# EPS_Local-Supply.net
KiCad netlist of a schematic drawn in Altium Designer
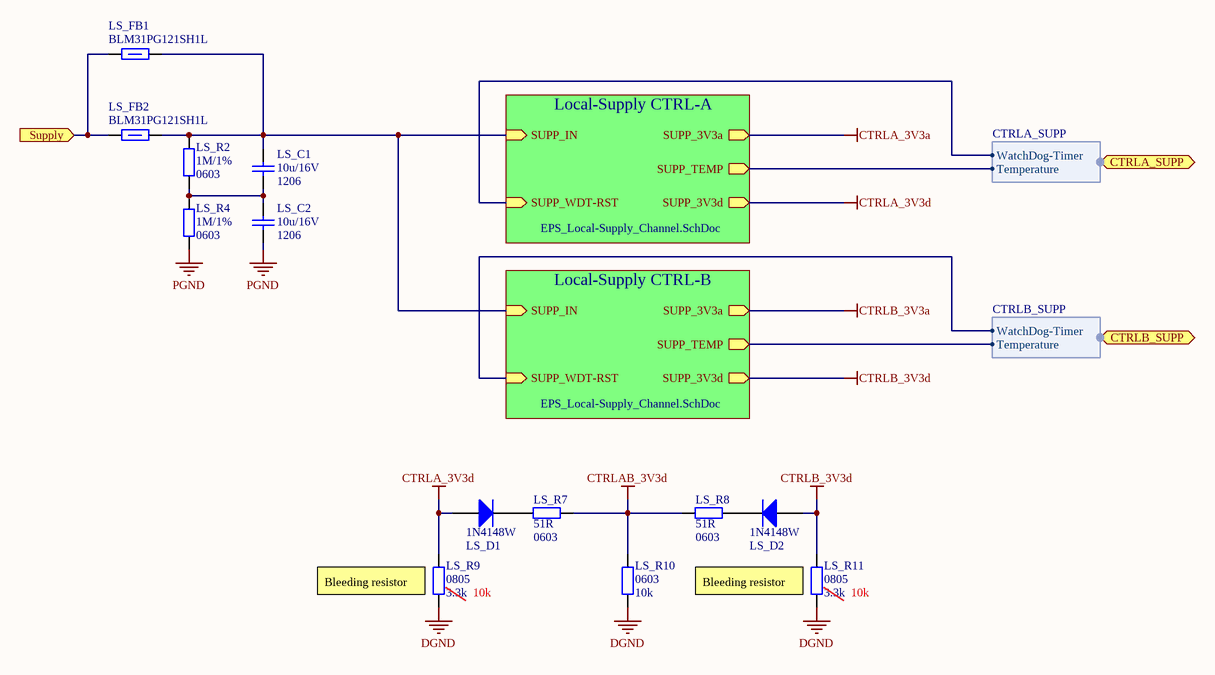
[diagram p0: EPS_Local-Supply.SchDoc]

(export (version "E")
  (design (tool "Eeschema 10.0.6"))
  (components
    (comp (ref "LS_C1")
      (value "10u/16V")
      (footprint "SMD_Capacitor_1206")
      (description "Ceramic Cap Kemet COTS 10u/16V X7R 1206")
      (fields
        (field (name "MANUFACTURERPARTNUMBER") "C1206T106K4RACTU")
        (field (name "MANUFACTURER") "Kemet")
        (field (name "PACKGE") "1206")
      )
      (libsource (lib "capacitors") (part "Cer_C1206T106K4RACTU"))
    )
    (comp (ref "LS_C2")
      (value "10u/16V")
      (footprint "SMD_Capacitor_1206")
      (description "Ceramic Cap Kemet COTS 10u/16V X7R 1206")
      (fields
        (field (name "MANUFACTURERPARTNUMBER") "C1206T106K4RACTU")
        (field (name "MANUFACTURER") "Kemet")
        (field (name "PACKGE") "1206")
      )
      (libsource (lib "capacitors") (part "Cer_C1206T106K4RACTU"))
    )
    (comp (ref "LS_D1")
      (value "1N4148W")
      (footprint "SOD-123")
      (description "Small Signal Fast Switching Diode")
      (fields (field (name "MANUFACTURER") "Vishay"))
      (libsource (lib "diodes") (part "1N4148W"))
    )
    (comp (ref "LS_D2")
      (value "1N4148W")
      (footprint "SOD-123")
      (description "Small Signal Fast Switching Diode")
      (fields (field (name "MANUFACTURER") "Vishay"))
      (libsource (lib "diodes") (part "1N4148W"))
    )
    (comp (ref "LS_FB1")
      (value "120R/100MHz")
      (footprint "SMD_FerriteBead_1206")
      (description "Ferrite bead, 1206, 0.02HM, 3.5A.")
      (fields (field (name "MANUFACTURER") "Murata") (field (name "MANUFACTURERPARTNUMBER") "BLM31PG121SH1L"))
      (libsource (lib "inductors") (part "BLM31PG121SH1L"))
    )
    (comp (ref "LS_FB2")
      (value "120R/100MHz")
      (footprint "SMD_FerriteBead_1206")
      (description "Ferrite bead, 1206, 0.02HM, 3.5A.")
      (fields (field (name "MANUFACTURER") "Murata") (field (name "MANUFACTURERPARTNUMBER") "BLM31PG121SH1L"))
      (libsource (lib "inductors") (part "BLM31PG121SH1L"))
    )
    (comp (ref "LS_R2")
      (value "1M/1%")
      (footprint "SMD_Resistor_0603")
      (fields (field (name "PACKAGE") "0603"))
      (libsource (lib "") (part "Res_1"))
    )
    (comp (ref "LS_R4")
      (value "1M/1%")
      (footprint "SMD_Resistor_0603")
      (fields (field (name "PACKAGE") "0603"))
      (libsource (lib "") (part "Res_1"))
    )
    (comp (ref "LS_R7")
      (value "51R")
      (footprint "SMD_Resistor_0603")
      (fields (field (name "PACKAGE") "0603"))
      (libsource (lib "resistors") (part "Res"))
    )
    (comp (ref "LS_R8")
      (value "51R")
      (footprint "SMD_Resistor_0603")
      (fields (field (name "PACKAGE") "0603"))
      (libsource (lib "resistors") (part "Res"))
    )
    (comp (ref "LS_R9")
      (value "3.3k")
      (footprint "SMD_Resistor_0805")
      (fields (field (name "PACKAGE") "0805"))
      (libsource (lib "resistors") (part "Res"))
    )
    (comp (ref "LS_R10")
      (value "10k")
      (footprint "SMD_Resistor_0603")
      (fields (field (name "PACKAGE") "0603"))
      (libsource (lib "resistors") (part "Res"))
    )
    (comp (ref "LS_R11")
      (value "3.3k")
      (footprint "SMD_Resistor_0805")
      (fields (field (name "PACKAGE") "0805"))
      (libsource (lib "resistors") (part "Res"))
    )
  )
  (nets
    (net (code "3") (name "/SUPP_IN") (class "Default")
      (node (ref "LS_C1") (pin "1") (pinfunction "1_1") (pintype "passive"))
      (node (ref "LS_FB1") (pin "2") (pinfunction "2_2") (pintype "passive"))
      (node (ref "LS_FB2") (pin "2") (pinfunction "2_2") (pintype "passive"))
      (node (ref "LS_R2") (pin "1") (pinfunction "1_1") (pintype "passive"))
    )
    (net (code "8") (name "/Supply") (class "Default")
      (node (ref "LS_FB1") (pin "1") (pinfunction "1_1") (pintype "passive"))
      (node (ref "LS_FB2") (pin "1") (pinfunction "1_1") (pintype "passive"))
    )
    (net (code "11") (name "CTRLAB_3V3d") (class "Default")
      (node (ref "LS_R10") (pin "2") (pinfunction "2_2") (pintype "passive"))
      (node (ref "LS_R7") (pin "2") (pinfunction "2_2") (pintype "passive"))
      (node (ref "LS_R8") (pin "1") (pinfunction "1_1") (pintype "passive"))
    )
    (net (code "13") (name "CTRLA_3V3d") (class "Default")
      (node (ref "LS_D1") (pin "A") (pinfunction "A_A") (pintype "passive"))
      (node (ref "LS_R9") (pin "2") (pinfunction "2_2") (pintype "passive"))
    )
    (net (code "15") (name "CTRLB_3V3d") (class "Default")
      (node (ref "LS_D2") (pin "A") (pinfunction "A_A") (pintype "passive"))
      (node (ref "LS_R11") (pin "2") (pinfunction "2_2") (pintype "passive"))
    )
    (net (code "16") (name "DGND") (class "Default")
      (node (ref "LS_R10") (pin "1") (pinfunction "1_1") (pintype "passive"))
      (node (ref "LS_R11") (pin "1") (pinfunction "1_1") (pintype "passive"))
      (node (ref "LS_R9") (pin "1") (pinfunction "1_1") (pintype "passive"))
    )
    (net (code "17") (name "Net-(LS_C1-Pad2)") (class "Default")
      (node (ref "LS_C1") (pin "2") (pinfunction "2_2") (pintype "passive"))
      (node (ref "LS_C2") (pin "1") (pinfunction "1_1") (pintype "passive"))
      (node (ref "LS_R2") (pin "2") (pinfunction "2_2") (pintype "passive"))
      (node (ref "LS_R4") (pin "1") (pinfunction "1_1") (pintype "passive"))
    )
    (net (code "18") (name "Net-(LS_D1-PadK)") (class "Default")
      (node (ref "LS_D1") (pin "K") (pinfunction "K_K") (pintype "passive"))
      (node (ref "LS_R7") (pin "1") (pinfunction "1_1") (pintype "passive"))
    )
    (net (code "19") (name "Net-(LS_D2-PadK)") (class "Default")
      (node (ref "LS_D2") (pin "K") (pinfunction "K_K") (pintype "passive"))
      (node (ref "LS_R8") (pin "2") (pinfunction "2_2") (pintype "passive"))
    )
    (net (code "20") (name "PGND") (class "Default")
      (node (ref "LS_C2") (pin "2") (pinfunction "2_2") (pintype "passive"))
      (node (ref "LS_R4") (pin "2") (pinfunction "2_2") (pintype "passive"))
    )
  )
)
